# leddriver.net
KiCad netlist of a schematic drawn in Altium Designer
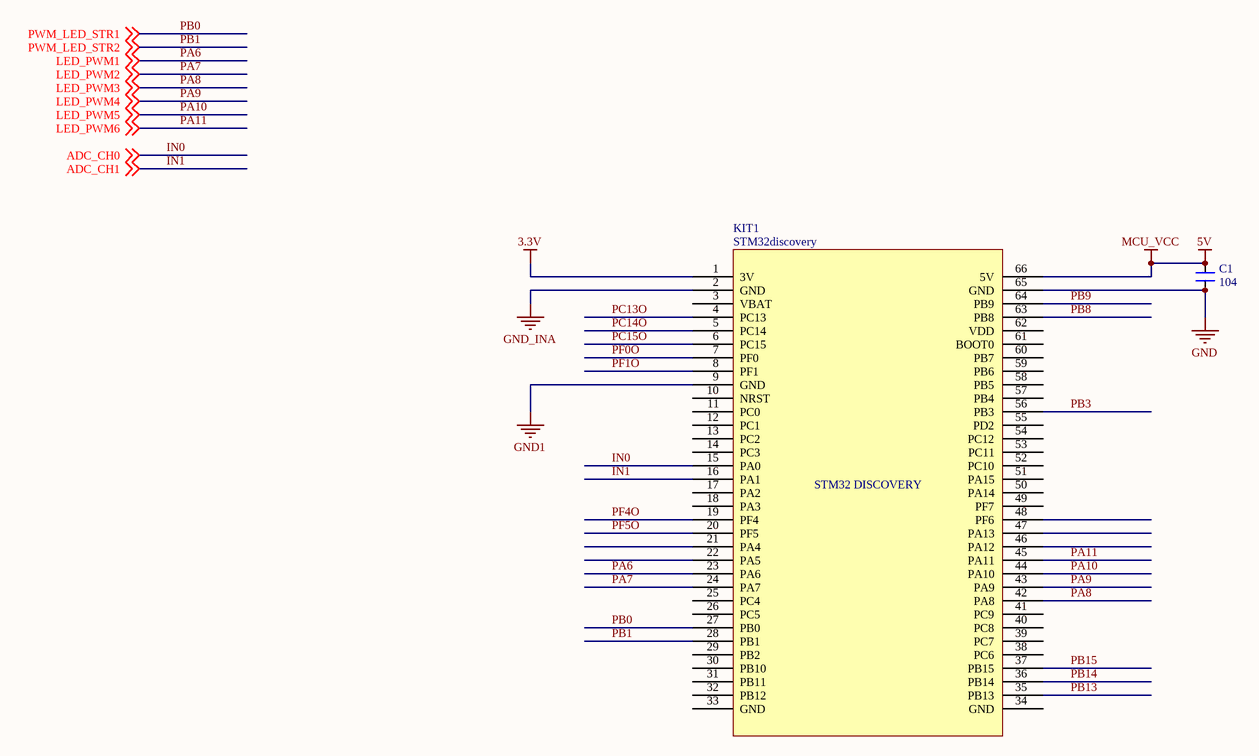
[diagram p0: leddriver.SchDoc]

(export (version "E")
  (design (tool "Eeschema 10.0.6"))
  (components
    (comp (ref "C1")
      (value "104")
      (footprint "0805_HV")
      (description "Cap SMD")
      (libsource (lib "hatcatbietbay") (part "CM"))
    )
    (comp (ref "KIT1")
      (value "STM32discovery")
      (footprint "STM32discovery_kit")
      (libsource (lib "Schlib1") (part "STM32Discovery_kit"))
    )
  )
  (nets
    (net (code "1") (name "/PB3") (class "Default")
      (node (ref "KIT1") (pin "56") (pinfunction "PB3_56") (pintype "passive"))
    )
    (net (code "2") (name "/PB8") (class "Default")
      (node (ref "KIT1") (pin "63") (pinfunction "PB8_63") (pintype "passive"))
    )
    (net (code "3") (name "/PB9") (class "Default")
      (node (ref "KIT1") (pin "64") (pinfunction "PB9_64") (pintype "passive"))
    )
    (net (code "4") (name "/PB13") (class "Default")
      (node (ref "KIT1") (pin "35") (pinfunction "PB13_35") (pintype "passive"))
    )
    (net (code "5") (name "/PB14") (class "Default")
      (node (ref "KIT1") (pin "36") (pinfunction "PB14_36") (pintype "passive"))
    )
    (net (code "6") (name "/PB15") (class "Default")
      (node (ref "KIT1") (pin "37") (pinfunction "PB15_37") (pintype "passive"))
    )
    (net (code "7") (name "/PC13O") (class "Default")
      (node (ref "KIT1") (pin "4") (pinfunction "PC13_4") (pintype "passive"))
    )
    (net (code "8") (name "/PC14O") (class "Default")
      (node (ref "KIT1") (pin "5") (pinfunction "PC14_5") (pintype "passive"))
    )
    (net (code "9") (name "/PC15O") (class "Default")
      (node (ref "KIT1") (pin "6") (pinfunction "PC15_6") (pintype "passive"))
    )
    (net (code "10") (name "/PF0O") (class "Default")
      (node (ref "KIT1") (pin "7") (pinfunction "PF0_7") (pintype "passive"))
    )
    (net (code "11") (name "/PF1O") (class "Default")
      (node (ref "KIT1") (pin "8") (pinfunction "PF1_8") (pintype "passive"))
    )
    (net (code "12") (name "/PF4O") (class "Default")
      (node (ref "KIT1") (pin "19") (pinfunction "PF4_19") (pintype "passive"))
    )
    (net (code "13") (name "/PF5O") (class "Default")
      (node (ref "KIT1") (pin "20") (pinfunction "PF5_20") (pintype "passive"))
    )
    (net (code "14") (name "3.3V") (class "Default")
      (node (ref "KIT1") (pin "1") (pinfunction "3V_1") (pintype "passive"))
    )
    (net (code "15") (name "5V") (class "Default")
      (node (ref "C1") (pin "2") (pinfunction "2_2") (pintype "passive"))
      (node (ref "KIT1") (pin "66") (pinfunction "5V_66") (pintype "passive"))
    )
    (net (code "16") (name "ADC_CH0") (class "Default")
      (node (ref "KIT1") (pin "15") (pinfunction "PA0_15") (pintype "passive"))
    )
    (net (code "17") (name "ADC_CH1") (class "Default")
      (node (ref "KIT1") (pin "16") (pinfunction "PA1_16") (pintype "passive"))
    )
    (net (code "18") (name "GND") (class "Default")
      (node (ref "C1") (pin "1") (pinfunction "1_1") (pintype "passive"))
      (node (ref "KIT1") (pin "65") (pinfunction "GND_65") (pintype "passive"))
    )
    (net (code "19") (name "GND1") (class "Default")
      (node (ref "KIT1") (pin "9") (pinfunction "GND_9") (pintype "passive"))
    )
    (net (code "20") (name "GND_INA") (class "Default")
      (node (ref "KIT1") (pin "2") (pinfunction "GND_2") (pintype "passive"))
    )
    (net (code "21") (name "LED_PWM1") (class "Default")
      (node (ref "KIT1") (pin "23") (pinfunction "PA6_23") (pintype "passive"))
    )
    (net (code "22") (name "LED_PWM2") (class "Default")
      (node (ref "KIT1") (pin "24") (pinfunction "PA7_24") (pintype "passive"))
    )
    (net (code "23") (name "LED_PWM3") (class "Default")
      (node (ref "KIT1") (pin "42") (pinfunction "PA8_42") (pintype "passive"))
    )
    (net (code "24") (name "LED_PWM4") (class "Default")
      (node (ref "KIT1") (pin "43") (pinfunction "PA9_43") (pintype "passive"))
    )
    (net (code "25") (name "LED_PWM5") (class "Default")
      (node (ref "KIT1") (pin "44") (pinfunction "PA10_44") (pintype "passive"))
    )
    (net (code "26") (name "LED_PWM6") (class "Default")
      (node (ref "KIT1") (pin "45") (pinfunction "PA11_45") (pintype "passive"))
    )
    (net (code "27") (name "PWM_LED_STR1") (class "Default")
      (node (ref "KIT1") (pin "27") (pinfunction "PB0_27") (pintype "passive"))
    )
    (net (code "28") (name "PWM_LED_STR2") (class "Default")
      (node (ref "KIT1") (pin "28") (pinfunction "PB1_28") (pintype "passive"))
    )
    (net (code "29") (name "unconnected-(KIT1-BOOT0-Pad61)") (class "Default")
      (node (ref "KIT1") (pin "61") (pinfunction "BOOT0_61") (pintype "passive"))
    )
    (net (code "30") (name "unconnected-(KIT1-GND-Pad33)") (class "Default")
      (node (ref "KIT1") (pin "33") (pinfunction "GND_33") (pintype "passive"))
    )
    (net (code "31") (name "unconnected-(KIT1-GND-Pad34)") (class "Default")
      (node (ref "KIT1") (pin "34") (pinfunction "GND_34") (pintype "passive"))
    )
    (net (code "32") (name "unconnected-(KIT1-NRST-Pad10)") (class "Default")
      (node (ref "KIT1") (pin "10") (pinfunction "NRST_10") (pintype "passive"))
    )
    (net (code "33") (name "unconnected-(KIT1-PA2-Pad17)") (class "Default")
      (node (ref "KIT1") (pin "17") (pinfunction "PA2_17") (pintype "passive"))
    )
    (net (code "34") (name "unconnected-(KIT1-PA3-Pad18)") (class "Default")
      (node (ref "KIT1") (pin "18") (pinfunction "PA3_18") (pintype "passive"))
    )
    (net (code "35") (name "unconnected-(KIT1-PA4-Pad21)") (class "Default")
      (node (ref "KIT1") (pin "21") (pinfunction "PA4_21") (pintype "passive"))
    )
    (net (code "36") (name "unconnected-(KIT1-PA5-Pad22)") (class "Default")
      (node (ref "KIT1") (pin "22") (pinfunction "PA5_22") (pintype "passive"))
    )
    (net (code "37") (name "unconnected-(KIT1-PA12-Pad46)") (class "Default")
      (node (ref "KIT1") (pin "46") (pinfunction "PA12_46") (pintype "passive"))
    )
    (net (code "38") (name "unconnected-(KIT1-PA13-Pad47)") (class "Default")
      (node (ref "KIT1") (pin "47") (pinfunction "PA13_47") (pintype "passive"))
    )
    (net (code "39") (name "unconnected-(KIT1-PA14-Pad50)") (class "Default")
      (node (ref "KIT1") (pin "50") (pinfunction "PA14_50") (pintype "passive"))
    )
    (net (code "40") (name "unconnected-(KIT1-PA15-Pad51)") (class "Default")
      (node (ref "KIT1") (pin "51") (pinfunction "PA15_51") (pintype "passive"))
    )
    (net (code "41") (name "unconnected-(KIT1-PB2-Pad29)") (class "Default")
      (node (ref "KIT1") (pin "29") (pinfunction "PB2_29") (pintype "passive"))
    )
    (net (code "42") (name "unconnected-(KIT1-PB4-Pad57)") (class "Default")
      (node (ref "KIT1") (pin "57") (pinfunction "PB4_57") (pintype "passive"))
    )
    (net (code "43") (name "unconnected-(KIT1-PB5-Pad58)") (class "Default")
      (node (ref "KIT1") (pin "58") (pinfunction "PB5_58") (pintype "passive"))
    )
    (net (code "44") (name "unconnected-(KIT1-PB6-Pad59)") (class "Default")
      (node (ref "KIT1") (pin "59") (pinfunction "PB6_59") (pintype "passive"))
    )
    (net (code "45") (name "unconnected-(KIT1-PB7-Pad60)") (class "Default")
      (node (ref "KIT1") (pin "60") (pinfunction "PB7_60") (pintype "passive"))
    )
    (net (code "46") (name "unconnected-(KIT1-PB10-Pad30)") (class "Default")
      (node (ref "KIT1") (pin "30") (pinfunction "PB10_30") (pintype "passive"))
    )
    (net (code "47") (name "unconnected-(KIT1-PB11-Pad31)") (class "Default")
      (node (ref "KIT1") (pin "31") (pinfunction "PB11_31") (pintype "passive"))
    )
    (net (code "48") (name "unconnected-(KIT1-PB12-Pad32)") (class "Default")
      (node (ref "KIT1") (pin "32") (pinfunction "PB12_32") (pintype "passive"))
    )
    (net (code "49") (name "unconnected-(KIT1-PC0-Pad11)") (class "Default")
      (node (ref "KIT1") (pin "11") (pinfunction "PC0_11") (pintype "passive"))
    )
    (net (code "50") (name "unconnected-(KIT1-PC1-Pad12)") (class "Default")
      (node (ref "KIT1") (pin "12") (pinfunction "PC1_12") (pintype "passive"))
    )
    (net (code "51") (name "unconnected-(KIT1-PC2-Pad13)") (class "Default")
      (node (ref "KIT1") (pin "13") (pinfunction "PC2_13") (pintype "passive"))
    )
    (net (code "52") (name "unconnected-(KIT1-PC3-Pad14)") (class "Default")
      (node (ref "KIT1") (pin "14") (pinfunction "PC3_14") (pintype "passive"))
    )
    (net (code "53") (name "unconnected-(KIT1-PC4-Pad25)") (class "Default")
      (node (ref "KIT1") (pin "25") (pinfunction "PC4_25") (pintype "passive"))
    )
    (net (code "54") (name "unconnected-(KIT1-PC5-Pad26)") (class "Default")
      (node (ref "KIT1") (pin "26") (pinfunction "PC5_26") (pintype "passive"))
    )
    (net (code "55") (name "unconnected-(KIT1-PC6-Pad38)") (class "Default")
      (node (ref "KIT1") (pin "38") (pinfunction "PC6_38") (pintype "passive"))
    )
    (net (code "56") (name "unconnected-(KIT1-PC7-Pad39)") (class "Default")
      (node (ref "KIT1") (pin "39") (pinfunction "PC7_39") (pintype "passive"))
    )
    (net (code "57") (name "unconnected-(KIT1-PC8-Pad40)") (class "Default")
      (node (ref "KIT1") (pin "40") (pinfunction "PC8_40") (pintype "passive"))
    )
    (net (code "58") (name "unconnected-(KIT1-PC9-Pad41)") (class "Default")
      (node (ref "KIT1") (pin "41") (pinfunction "PC9_41") (pintype "passive"))
    )
    (net (code "59") (name "unconnected-(KIT1-PC10-Pad52)") (class "Default")
      (node (ref "KIT1") (pin "52") (pinfunction "PC10_52") (pintype "passive"))
    )
    (net (code "60") (name "unconnected-(KIT1-PC11-Pad53)") (class "Default")
      (node (ref "KIT1") (pin "53") (pinfunction "PC11_53") (pintype "passive"))
    )
    (net (code "61") (name "unconnected-(KIT1-PC12-Pad54)") (class "Default")
      (node (ref "KIT1") (pin "54") (pinfunction "PC12_54") (pintype "passive"))
    )
    (net (code "62") (name "unconnected-(KIT1-PD2-Pad55)") (class "Default")
      (node (ref "KIT1") (pin "55") (pinfunction "PD2_55") (pintype "passive"))
    )
    (net (code "63") (name "unconnected-(KIT1-PF6-Pad48)") (class "Default")
      (node (ref "KIT1") (pin "48") (pinfunction "PF6_48") (pintype "passive"))
    )
    (net (code "64") (name "unconnected-(KIT1-PF7-Pad49)") (class "Default")
      (node (ref "KIT1") (pin "49") (pinfunction "PF7_49") (pintype "passive"))
    )
    (net (code "65") (name "unconnected-(KIT1-VBAT-Pad3)") (class "Default")
      (node (ref "KIT1") (pin "3") (pinfunction "VBAT_3") (pintype "passive"))
    )
    (net (code "66") (name "unconnected-(KIT1-VDD-Pad62)") (class "Default")
      (node (ref "KIT1") (pin "62") (pinfunction "VDD_62") (pintype "passive"))
    )
  )
)
